# -11_04_00.net
KiCad netlist of a schematic drawn in Altium Designer
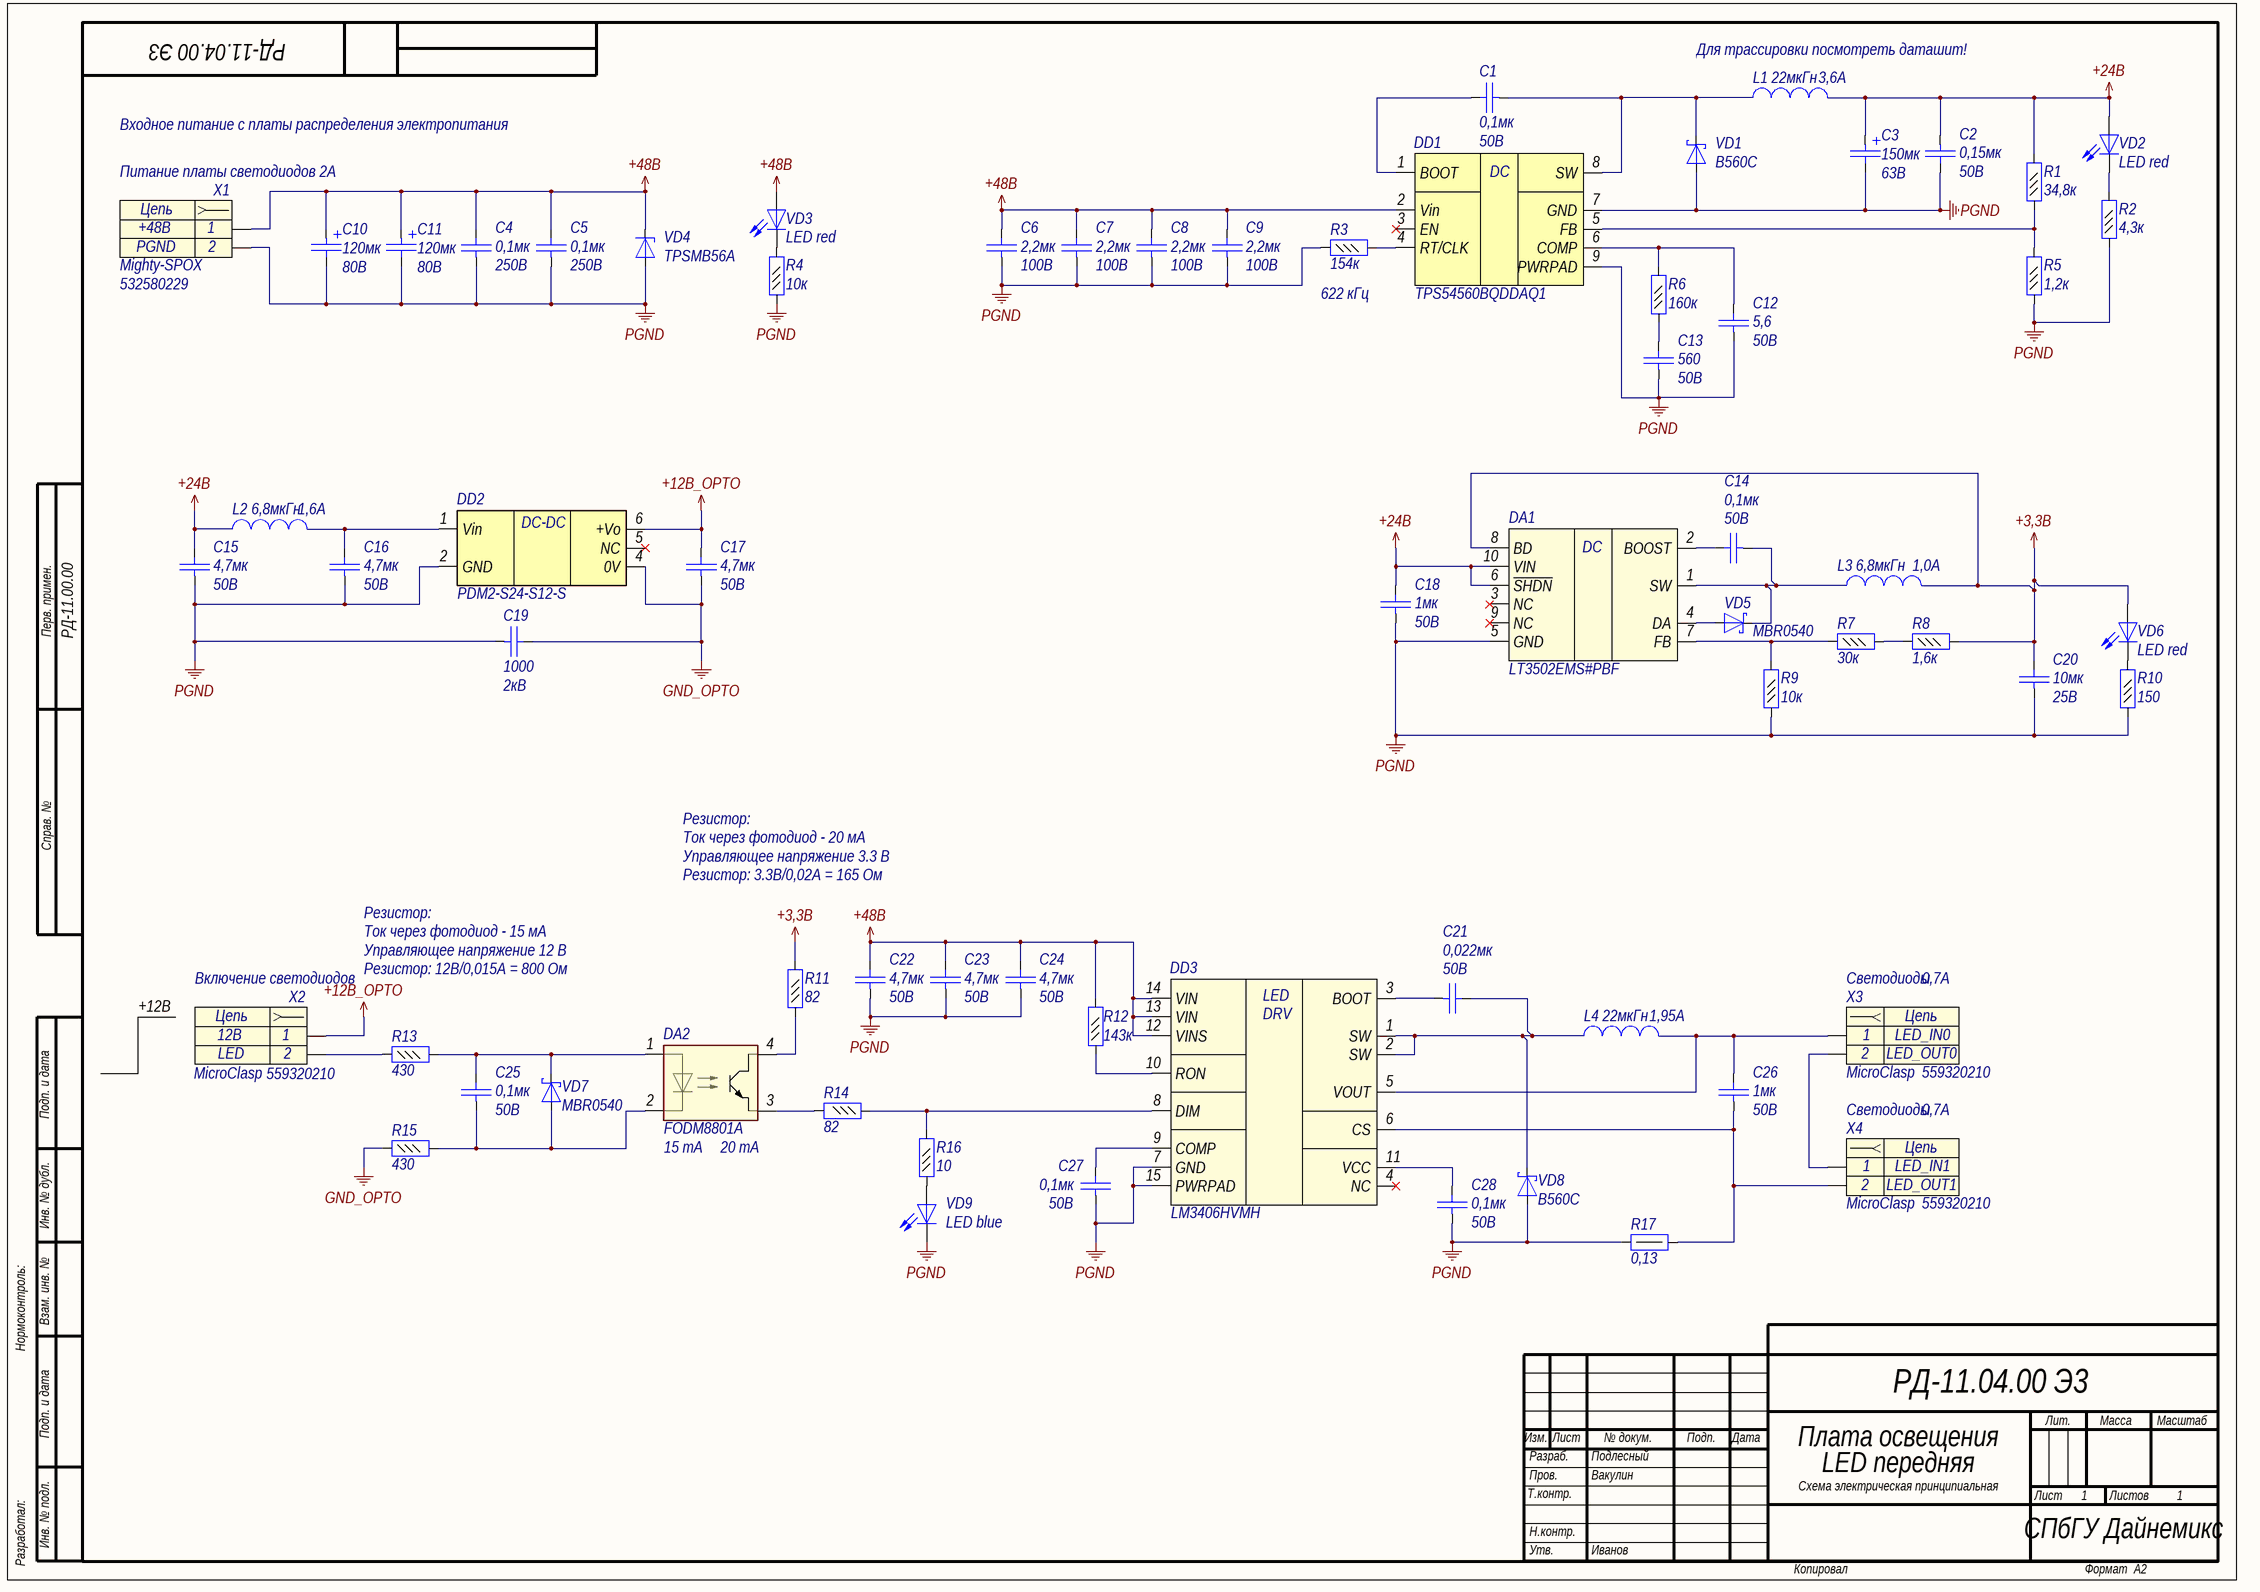
[diagram p0: РД-11.04.00.SchDoc]

(export (version "E")
  (design (tool "Eeschema 10.0.6"))
  (components
    (comp (ref "C1")
      (value "0,1мк")
      (footprint "C0603")
      (description "Конденсатор")
      (fields (field (name "VOLTAGE") "50B") (field (name "PART NUMBER") "GRM188R71H104KA93D"))
      (libsource (lib "MOP44") (part "Capacitor"))
    )
    (comp (ref "C2")
      (value "0,15мк")
      (footprint "C1812")
      (description "Конденсатор")
      (fields (field (name "VOLTAGE") "50В") (field (name "PART NUMBER") "C4532C0G1H154J250KA "))
      (libsource (lib "MOP44") (part "Capacitor"))
    )
    (comp (ref "C3")
      (value "150мк")
      (footprint "Cap_SMD_radial_polar(10x16.5)")
      (description "Конденсатор полярный")
      (fields
        (field (name "VOLTAGE") "63B")
        (field (name "PART NUMBER") "EEH-ZS1J151P")
        (field (name "Comment") "Capacitor_pol")
      )
      (libsource (lib "MOP44") (part "Capacitor_pol"))
    )
    (comp (ref "C4")
      (value "0,1мк")
      (footprint "C1206")
      (description "Конденсатор")
      (fields
        (field (name "VOLTAGE") "250В")
        (field (name "PART NUMBER") "GRM31CR72E104K")
        (field (name "Comment") "Capacitor")
      )
      (libsource (lib "MOP44") (part "Capacitor"))
    )
    (comp (ref "C5")
      (value "0,1мк")
      (footprint "C1206")
      (description "Конденсатор")
      (fields
        (field (name "VOLTAGE") "250В")
        (field (name "PART NUMBER") "GRM31CR72E104K")
        (field (name "Comment") "Capacitor")
      )
      (libsource (lib "MOP44") (part "Capacitor"))
    )
    (comp (ref "C6")
      (value "2,2мк")
      (footprint "C1812")
      (description "Конденсатор")
      (fields (field (name "VOLTAGE") "100В") (field (name "PART NUMBER") "C4532X7R2A225M"))
      (libsource (lib "MOP44") (part "Capacitor"))
    )
    (comp (ref "C7")
      (value "2,2мк")
      (footprint "C1812")
      (description "Конденсатор")
      (fields (field (name "VOLTAGE") "100В") (field (name "PART NUMBER") "C4532X7R2A225M"))
      (libsource (lib "MOP44") (part "Capacitor"))
    )
    (comp (ref "C8")
      (value "2,2мк")
      (footprint "C1812")
      (description "Конденсатор")
      (fields (field (name "VOLTAGE") "100В") (field (name "PART NUMBER") "C4532X7R2A225M"))
      (libsource (lib "MOP44") (part "Capacitor"))
    )
    (comp (ref "C9")
      (value "2,2мк")
      (footprint "C1812")
      (description "Конденсатор")
      (fields (field (name "VOLTAGE") "100В") (field (name "PART NUMBER") "C4532X7R2A225M"))
      (libsource (lib "MOP44") (part "Capacitor"))
    )
    (comp (ref "C10")
      (value "120мк")
      (footprint "K50-35(8X20)_H")
      (description "Конденсатор полярный")
      (fields
        (field (name "VOLTAGE") "80В")
        (field (name "PART NUMBER") "EEU-FS1K121LB")
        (field (name "Comment") "Capacitor_pol")
      )
      (libsource (lib "MOP44") (part "Capacitor_pol"))
    )
    (comp (ref "C11")
      (value "120мк")
      (footprint "K50-35(8X20)_H")
      (description "Конденсатор полярный")
      (fields
        (field (name "VOLTAGE") "80В")
        (field (name "PART NUMBER") "EEU-FS1K121LB")
        (field (name "Comment") "Capacitor_pol")
      )
      (libsource (lib "MOP44") (part "Capacitor_pol"))
    )
    (comp (ref "C12")
      (value "5,6")
      (footprint "C0603")
      (description "Конденсатор")
      (fields (field (name "VOLTAGE") "50B") (field (name "PART NUMBER") "GRM1885C1H5R6C*"))
      (libsource (lib "MOP44") (part "Capacitor"))
    )
    (comp (ref "C13")
      (value "560")
      (footprint "C0603")
      (description "Конденсатор")
      (fields (field (name "VOLTAGE") "50B") (field (name "PART NUMBER") "GRM1885C1H561J"))
      (libsource (lib "MOP44") (part "Capacitor"))
    )
    (comp (ref "C14")
      (value "0,1мк")
      (footprint "C0603")
      (description "Конденсатор")
      (fields (field (name "VOLTAGE") "50B") (field (name "PART NUMBER") "GRM188R71H104KA93D"))
      (libsource (lib "MOP44") (part "Capacitor"))
    )
    (comp (ref "C15")
      (value "4,7мк")
      (footprint "C1206")
      (description "Конденсатор")
      (fields (field (name "VOLTAGE") "50В") (field (name "PART NUMBER") "GRM31CR71H475KA12L"))
      (libsource (lib "MOP44") (part "Capacitor"))
    )
    (comp (ref "C16")
      (value "4,7мк")
      (footprint "C1206")
      (description "Конденсатор")
      (fields (field (name "VOLTAGE") "50В") (field (name "PART NUMBER") "GRM31CR71H475KA12L"))
      (libsource (lib "MOP44") (part "Capacitor"))
    )
    (comp (ref "C17")
      (value "4,7мк")
      (footprint "C1206")
      (description "Конденсатор")
      (fields (field (name "VOLTAGE") "50В") (field (name "PART NUMBER") "GRM31CR71H475KA12L"))
      (libsource (lib "MOP44") (part "Capacitor"))
    )
    (comp (ref "C18")
      (value "1мк")
      (footprint "C0805")
      (description "Конденсатор")
      (fields
        (field (name "VOLTAGE") "50B")
        (field (name "PART NUMBER") "GRM21BR71H105K")
        (field (name "Comment") "Capacitor")
      )
      (libsource (lib "MOP44") (part "Capacitor"))
    )
    (comp (ref "C19")
      (value "1000")
      (footprint "C1808")
      (description "Конденсатор")
      (fields (field (name "VOLTAGE") "2кB") (field (name "PART NUMBER") "GR442QR73D102KW01L"))
      (libsource (lib "MOP44") (part "Capacitor"))
    )
    (comp (ref "C20")
      (value "10мк")
      (footprint "C1206")
      (description "Конденсатор")
      (fields
        (field (name "VOLTAGE") "25В")
        (field (name "PART NUMBER") "GRM31CR71E106KA12L*")
        (field (name "Comment") "Capacitor")
      )
      (libsource (lib "MOP44") (part "Capacitor"))
    )
    (comp (ref "C21")
      (value "0,022мк")
      (footprint "C0603")
      (description "Конденсатор")
      (fields (field (name "VOLTAGE") "50B") (field (name "PART NUMBER") "GRM188R71H223K**"))
      (libsource (lib "MOP44") (part "Capacitor"))
    )
    (comp (ref "C22")
      (value "4,7мк")
      (footprint "C1206")
      (description "Конденсатор")
      (fields (field (name "VOLTAGE") "50В") (field (name "PART NUMBER") "GRM31CR71H475KA12L"))
      (libsource (lib "MOP44") (part "Capacitor"))
    )
    (comp (ref "C23")
      (value "4,7мк")
      (footprint "C1206")
      (description "Конденсатор")
      (fields (field (name "VOLTAGE") "50В") (field (name "PART NUMBER") "GRM31CR71H475KA12L"))
      (libsource (lib "MOP44") (part "Capacitor"))
    )
    (comp (ref "C24")
      (value "4,7мк")
      (footprint "C1206")
      (description "Конденсатор")
      (fields (field (name "VOLTAGE") "50В") (field (name "PART NUMBER") "GRM31CR71H475KA12L"))
      (libsource (lib "MOP44") (part "Capacitor"))
    )
    (comp (ref "C25")
      (value "0,1мк")
      (footprint "C0603")
      (description "Конденсатор")
      (fields (field (name "VOLTAGE") "50B") (field (name "PART NUMBER") "GRM188R71H104KA93D"))
      (libsource (lib "MOP44") (part "Capacitor"))
    )
    (comp (ref "C26")
      (value "1мк")
      (footprint "C0805")
      (description "Конденсатор")
      (fields
        (field (name "VOLTAGE") "50B")
        (field (name "PART NUMBER") "GRM21BR71H105K")
        (field (name "Comment") "Capacitor")
      )
      (libsource (lib "MOP44") (part "Capacitor"))
    )
    (comp (ref "C27")
      (value "0,1мк")
      (footprint "C0603")
      (description "Конденсатор")
      (fields (field (name "VOLTAGE") "50B") (field (name "PART NUMBER") "GRM188R71H104KA93D"))
      (libsource (lib "MOP44") (part "Capacitor"))
    )
    (comp (ref "C28")
      (value "0,1мк")
      (footprint "C0603")
      (description "Конденсатор")
      (fields (field (name "VOLTAGE") "50B") (field (name "PART NUMBER") "GRM188R71H104KA93D"))
      (libsource (lib "MOP44") (part "Capacitor"))
    )
    (comp (ref "DA1")
      (value "LT3502_MS")
      (footprint "MSOP10")
      (description "1.1MHz/2.2MHz, 500mA  Step-Down Regulators")
      (fields (field (name "PART NUMBER") "LT3502EMS#PBF") (field (name "MANUFACTURER") "Linear Technology"))
      (libsource (lib "MOP44") (part "LT3502_MS"))
    )
    (comp (ref "DA2")
      (value "OPTO-1")
      (footprint "Miniflat4")
      (description "Опторазвязка")
      (fields (field (name "PART NUMBER") "FODM8801A") (field (name "MANUFACTURER") "ON Semiconductor"))
      (libsource (lib "MOP44") (part "OPTO-1"))
    )
    (comp (ref "DD1")
      (value "TPS54560")
      (footprint "SO Powerpad8")
      (description "5-A, Wide Input Range, Step-Down Converter")
      (fields
        (field (name "PART NUMBER") "TPS54560BQDDAQ1")
        (field (name "MANUFACTURER") "Texas Instruments")
      )
      (libsource (lib "MOP44") (part "TPS54560"))
    )
    (comp (ref "DD2")
      (value "PDM2-Sxx-Sxx-S")
      (footprint "SIP6")
      (description "DC/DC преобразователь изолированный")
      (fields (field (name "PART NUMBER") "PDM2-S24-S12-S") (field (name "MANUFACTURER") "CUI INC"))
      (libsource (lib "MOP44") (part "PDM2-Sxx-Sxx-S"))
    )
    (comp (ref "DD3")
      (value "LM3406")
      (footprint "TSSOP14 POWERPAD")
      (description "1.5A Constant Current Buck Regulator for Driving High  Power LEDs")
      (fields (field (name "PART NUMBER") "LM3406HVMH"))
      (libsource (lib "MOP44") (part "LM3406"))
    )
    (comp (ref "L1")
      (value "22мкГн")
      (footprint "IND_12.5x12.5")
      (description "EMI Suppression Filter")
      (fields
        (field (name "RATED CURRENT") "3,6A")
        (field (name "PART NUMBER") "B82477G4223M000")
        (field (name "Comment") "Inductor")
      )
      (libsource (lib "MOP44") (part "Inductor"))
    )
    (comp (ref "L2")
      (value "6,8мкГн")
      (footprint "SDR0604")
      (description "EMI Suppression Filter")
      (fields
        (field (name "RATED CURRENT") "1,6A")
        (field (name "PART NUMBER") "SDR0604-6R8ML")
        (field (name "Comment") "Inductor")
      )
      (libsource (lib "MOP44") (part "Inductor"))
    )
    (comp (ref "L3")
      (value "6,8мкГн")
      (footprint "SDR0302")
      (description "EMI Suppression Filter")
      (fields
        (field (name "RATED CURRENT") "1,0A")
        (field (name "PART NUMBER") "SDR0302-6R8ML")
        (field (name "Comment") "Inductor")
      )
      (libsource (lib "MOP44") (part "Inductor"))
    )
    (comp (ref "L4")
      (value "22мкГн")
      (footprint "SDR1006")
      (description "EMI Suppression Filter")
      (fields
        (field (name "RATED CURRENT") "1,95A")
        (field (name "PART NUMBER") "SDR1006- 220ML")
        (field (name "Comment") "Inductor")
      )
      (libsource (lib "MOP44") (part "Inductor"))
    )
    (comp (ref "R1")
      (value "34,8к")
      (footprint "R0603")
      (description "Резистор")
      (fields (field (name "PART NUMBER") "RC0603FR-0734K8L") (field (name "POWER") "0,062Вт"))
      (libsource (lib "") (part "Resistor_0,062Вт_1"))
    )
    (comp (ref "R2")
      (value "4,3к")
      (footprint "R0603")
      (description "Резистор")
      (fields (field (name "PART NUMBER") "RC0603FR-074K3") (field (name "POWER") "0,062Вт"))
      (libsource (lib "") (part "Resistor_0,062Вт_1"))
    )
    (comp (ref "R3")
      (value "154к")
      (footprint "R0603")
      (description "Резистор")
      (fields (field (name "PART NUMBER") "RC0603FR-07154KL") (field (name "POWER") "0,062Вт"))
      (libsource (lib "MOP44") (part "Resistor_0,062Вт"))
    )
    (comp (ref "R4")
      (value "10к")
      (footprint "R0603")
      (description "Резистор")
      (fields (field (name "PART NUMBER") "RC0603FR-0710KL") (field (name "POWER") "0,062Вт"))
      (libsource (lib "") (part "Resistor_0,062Вт_1"))
    )
    (comp (ref "R5")
      (value "1,2к")
      (footprint "R0603")
      (description "Резистор")
      (fields (field (name "PART NUMBER") "RC0603FR-071K2") (field (name "POWER") "0,062Вт"))
      (libsource (lib "") (part "Resistor_0,062Вт_1"))
    )
    (comp (ref "R6")
      (value "160к")
      (footprint "R0603")
      (description "Резистор")
      (fields (field (name "PART NUMBER") "RC0603FR-07160KL") (field (name "POWER") "0,062Вт"))
      (libsource (lib "") (part "Resistor_0,062Вт_1"))
    )
    (comp (ref "R7")
      (value "30к")
      (footprint "R0603")
      (description "Резистор")
      (fields (field (name "PART NUMBER") "RC0603FR-0730KL") (field (name "POWER") "0,062Вт"))
      (libsource (lib "MOP44") (part "Resistor_0,062Вт"))
    )
    (comp (ref "R8")
      (value "1,6к")
      (footprint "R0603")
      (description "Резистор")
      (fields (field (name "PART NUMBER") "RC0603FR-071K6") (field (name "POWER") "0,062Вт"))
      (libsource (lib "MOP44") (part "Resistor_0,062Вт"))
    )
    (comp (ref "R9")
      (value "10к")
      (footprint "R0603")
      (description "Резистор")
      (fields (field (name "PART NUMBER") "RC0603FR-0710KL") (field (name "POWER") "0,062Вт"))
      (libsource (lib "") (part "Resistor_0,062Вт_1"))
    )
    (comp (ref "R10")
      (value "150")
      (footprint "R0603")
      (description "Резистор")
      (fields (field (name "PART NUMBER") "RC0603FR-07150RL") (field (name "POWER") "0,062Вт"))
      (libsource (lib "") (part "Resistor_0,062Вт_1"))
    )
    (comp (ref "R11")
      (value "82")
      (footprint "R0603")
      (description "Резистор")
      (fields (field (name "PART NUMBER") "RC0603FR-0782RL") (field (name "POWER") "0,062Вт"))
      (libsource (lib "") (part "Resistor_0,062Вт_1"))
    )
    (comp (ref "R12")
      (value "143к")
      (footprint "R0603")
      (description "Резистор")
      (fields (field (name "PART NUMBER") "RC0603FR-07143KL") (field (name "POWER") "0,062Вт"))
      (libsource (lib "") (part "Resistor_0,062Вт_1"))
    )
    (comp (ref "R13")
      (value "430")
      (footprint "R0603")
      (description "Резистор")
      (fields (field (name "PART NUMBER") "RC0603FR-07430RL") (field (name "POWER") "0,062Вт"))
      (libsource (lib "MOP44") (part "Resistor_0,062Вт"))
    )
    (comp (ref "R14")
      (value "82")
      (footprint "R0603")
      (description "Резистор")
      (fields (field (name "PART NUMBER") "RC0603FR-0782RL") (field (name "POWER") "0,062Вт"))
      (libsource (lib "") (part "Resistor_0,062Вт_2"))
    )
    (comp (ref "R15")
      (value "430")
      (footprint "R0603")
      (description "Резистор")
      (fields (field (name "PART NUMBER") "RC0603FR-07430RL") (field (name "POWER") "0,062Вт"))
      (libsource (lib "MOP44") (part "Resistor_0,062Вт"))
    )
    (comp (ref "R16")
      (value "10")
      (footprint "R0603")
      (description "Резистор")
      (fields (field (name "PART NUMBER") "RC0603FR-0710RL") (field (name "POWER") "0,062Вт"))
      (libsource (lib "") (part "Resistor_0,062Вт_1"))
    )
    (comp (ref "R17")
      (value "0,13")
      (footprint "R2010")
      (description "Резистор")
      (fields (field (name "PART NUMBER") "CRL2010-FW-R130ELF") (field (name "POWER") "0,5Вт"))
      (libsource (lib "MOP44") (part "Resistor_0,5Вт"))
    )
    (comp (ref "VD1")
      (value "DiodeSchottky")
      (footprint "SMC")
      (description "Диод Шоттки")
      (fields (field (name "PART NUMBER") "B560C"))
      (libsource (lib "MOP44") (part "DiodeSchottky"))
    )
    (comp (ref "VD2")
      (value "LED")
      (footprint "L_0603_RED")
      (description "Светодиод")
      (fields (field (name "PART NAME") "LED red") (field (name "PART NUMBER") "TO-1608BC-MRE"))
      (libsource (lib "MOP44") (part "LED"))
    )
    (comp (ref "VD3")
      (value "LED")
      (footprint "L_0603_RED")
      (description "Светодиод")
      (fields (field (name "PART NAME") "LED red") (field (name "PART NUMBER") "TO-1608BC-MRE"))
      (libsource (lib "MOP44") (part "LED"))
    )
    (comp (ref "VD4")
      (value "DiodeZener")
      (footprint "SMB")
      (description "Cтабилитрон (лавинный выпрямительный диод) односторонний")
      (fields (field (name "PART NUMBER") "TPSMB56A"))
      (libsource (lib "MOP44") (part "DiodeZener"))
    )
    (comp (ref "VD5")
      (value "DiodeSchottky")
      (footprint "SOD-123")
      (description "Диод Шоттки")
      (fields (field (name "PART NUMBER") "MBR0540"))
      (libsource (lib "MOP44") (part "DiodeSchottky"))
    )
    (comp (ref "VD6")
      (value "LED")
      (footprint "L_0603_RED")
      (description "Светодиод")
      (fields (field (name "PART NAME") "LED red") (field (name "PART NUMBER") "TO-1608BC-MRE"))
      (libsource (lib "MOP44") (part "LED"))
    )
    (comp (ref "VD7")
      (value "DiodeSchottky")
      (footprint "SOD-123")
      (description "Диод Шоттки")
      (fields (field (name "PART NUMBER") "MBR0540"))
      (libsource (lib "MOP44") (part "DiodeSchottky"))
    )
    (comp (ref "VD8")
      (value "DiodeSchottky")
      (footprint "SMC")
      (description "Диод Шоттки")
      (fields (field (name "PART NUMBER") "B560C"))
      (libsource (lib "MOP44") (part "DiodeSchottky"))
    )
    (comp (ref "VD9")
      (value "LED")
      (footprint "L_0603_BLUE")
      (description "Светодиод")
      (fields (field (name "PART NAME") "LED blue") (field (name "PART NUMBER") "TO-1608BC-BF"))
      (libsource (lib "MOP44") (part "LED"))
    )
    (comp (ref "X1")
      (value "Питание платы светодиодов 2А")
      (footprint "MOLEX_532580229")
      (description "Разъем - 2 конт. розетка")
      (fields (field (name "PART NAME") "Mighty-SPOX") (field (name "PART NUMBER") "532580229"))
      (libsource (lib "") (part "Header_2_sct_1"))
    )
    (comp (ref "X2")
      (value "Включение светодиодов")
      (footprint "MOLEX_559320210")
      (description "Разъем - 2 конт. розетка")
      (fields (field (name "PART NAME") "MicroClasp") (field (name "PART NUMBER") "559320210"))
      (libsource (lib "") (part "Header_2_sct_1"))
    )
    (comp (ref "X3")
      (value "Cветодиоды")
      (footprint "MOLEX_559320210")
      (description "Разъем - 2 конт. розетка")
      (fields (field (name "PART NAME") "MicroClasp") (field (name "PART NUMBER") "559320210"))
      (libsource (lib "MOP44") (part "Header_2_sct"))
    )
    (comp (ref "X4")
      (value "Cветодиоды")
      (footprint "MOLEX_559320210")
      (description "Разъем - 2 конт. розетка")
      (fields (field (name "PART NAME") "MicroClasp") (field (name "PART NUMBER") "559320210"))
      (libsource (lib "MOP44") (part "Header_2_sct"))
    )
  )
  (nets
    (net (code "1") (name "+3,3B") (class "Default")
      (node (ref "C20") (pin "2") (pinfunction "2_2") (pintype "passive"))
      (node (ref "DA1") (pin "8") (pinfunction "BD_8") (pintype "power_in"))
      (node (ref "L3") (pin "2") (pinfunction "2_2") (pintype "passive"))
      (node (ref "R11") (pin "2") (pinfunction "2_2") (pintype "passive"))
      (node (ref "R8") (pin "2") (pinfunction "2_2") (pintype "passive"))
      (node (ref "VD6") (pin "2") (pinfunction "A_2") (pintype "passive"))
    )
    (net (code "2") (name "+12B_OPTO") (class "Default")
      (node (ref "C17") (pin "2") (pinfunction "2_2") (pintype "passive"))
      (node (ref "DD2") (pin "6") (pinfunction "+Vo_6") (pintype "passive"))
      (node (ref "X2") (pin "1") (pinfunction "1_1") (pintype "passive"))
    )
    (net (code "3") (name "+24B") (class "Default")
      (node (ref "C15") (pin "2") (pinfunction "2_2") (pintype "passive"))
      (node (ref "C18") (pin "2") (pinfunction "2_2") (pintype "passive"))
      (node (ref "C2") (pin "1") (pinfunction "1_1") (pintype "passive"))
      (node (ref "C3") (pin "1") (pinfunction "1_1") (pintype "passive"))
      (node (ref "DA1") (pin "10") (pinfunction "VIN_10") (pintype "power_in"))
      (node (ref "DA1") (pin "6") (pinfunction "~{SHDN}_6") (pintype "power_in"))
      (node (ref "L1") (pin "2") (pinfunction "2_2") (pintype "passive"))
      (node (ref "L2") (pin "1") (pinfunction "1_1") (pintype "passive"))
      (node (ref "R1") (pin "2") (pinfunction "2_2") (pintype "passive"))
      (node (ref "VD2") (pin "2") (pinfunction "A_2") (pintype "passive"))
    )
    (net (code "4") (name "+48B") (class "Default")
      (node (ref "C10") (pin "1") (pinfunction "1_1") (pintype "passive"))
      (node (ref "C11") (pin "1") (pinfunction "1_1") (pintype "passive"))
      (node (ref "C22") (pin "2") (pinfunction "2_2") (pintype "passive"))
      (node (ref "C23") (pin "2") (pinfunction "2_2") (pintype "passive"))
      (node (ref "C24") (pin "2") (pinfunction "2_2") (pintype "passive"))
      (node (ref "C4") (pin "2") (pinfunction "2_2") (pintype "passive"))
      (node (ref "C5") (pin "2") (pinfunction "2_2") (pintype "passive"))
      (node (ref "C6") (pin "2") (pinfunction "2_2") (pintype "passive"))
      (node (ref "C7") (pin "2") (pinfunction "2_2") (pintype "passive"))
      (node (ref "C8") (pin "2") (pinfunction "2_2") (pintype "passive"))
      (node (ref "C9") (pin "2") (pinfunction "2_2") (pintype "passive"))
      (node (ref "DD1") (pin "2") (pinfunction "Vin_2") (pintype "passive"))
      (node (ref "DD3") (pin "12") (pinfunction "VINS_12") (pintype "passive"))
      (node (ref "DD3") (pin "13") (pinfunction "VIN_13") (pintype "passive"))
      (node (ref "DD3") (pin "14") (pinfunction "VIN_14") (pintype "passive"))
      (node (ref "R12") (pin "2") (pinfunction "2_2") (pintype "passive"))
      (node (ref "VD3") (pin "2") (pinfunction "A_2") (pintype "passive"))
      (node (ref "VD4") (pin "1") (pinfunction "K_1") (pintype "passive"))
      (node (ref "X1") (pin "1") (pinfunction "1_1") (pintype "passive"))
    )
    (net (code "5") (name "GND_OPTO") (class "Default")
      (node (ref "C17") (pin "1") (pinfunction "1_1") (pintype "passive"))
      (node (ref "C19") (pin "2") (pinfunction "2_2") (pintype "passive"))
      (node (ref "DD2") (pin "4") (pinfunction "0V_4") (pintype "passive"))
      (node (ref "R15") (pin "1") (pinfunction "1_1") (pintype "passive"))
    )
    (net (code "6") (name "Net-(C13-Pad2)") (class "Default")
      (node (ref "C13") (pin "2") (pinfunction "2_2") (pintype "passive"))
      (node (ref "R6") (pin "1") (pinfunction "1_1") (pintype "passive"))
    )
    (net (code "7") (name "Net-(DA1-BOOST)") (class "Default")
      (node (ref "C14") (pin "2") (pinfunction "2_2") (pintype "passive"))
      (node (ref "DA1") (pin "2") (pinfunction "BOOST_2") (pintype "power_in"))
    )
    (net (code "8") (name "Net-(DA1-DA)") (class "Default")
      (node (ref "DA1") (pin "4") (pinfunction "DA_4") (pintype "power_in"))
      (node (ref "VD5") (pin "2") (pinfunction "A_2") (pintype "passive"))
    )
    (net (code "9") (name "Net-(DA1-FB)") (class "Default")
      (node (ref "DA1") (pin "7") (pinfunction "FB_7") (pintype "power_in"))
      (node (ref "R7") (pin "1") (pinfunction "1_1") (pintype "passive"))
      (node (ref "R9") (pin "2") (pinfunction "2_2") (pintype "passive"))
    )
    (net (code "10") (name "Net-(DA1-SW)") (class "Default")
      (node (ref "C14") (pin "1") (pinfunction "1_1") (pintype "passive"))
      (node (ref "DA1") (pin "1") (pinfunction "SW_1") (pintype "power_in"))
      (node (ref "L3") (pin "1") (pinfunction "1_1") (pintype "passive"))
      (node (ref "VD5") (pin "1") (pinfunction "K_1") (pintype "passive"))
    )
    (net (code "11") (name "Net-(DA2-Pad3)") (class "Default")
      (node (ref "DA2") (pin "3") (pintype "passive"))
      (node (ref "R14") (pin "2") (pinfunction "2_2") (pintype "passive"))
    )
    (net (code "12") (name "Net-(DA2-Pad4)") (class "Default")
      (node (ref "DA2") (pin "4") (pintype "passive"))
      (node (ref "R11") (pin "1") (pinfunction "1_1") (pintype "passive"))
    )
    (net (code "13") (name "Net-(DD1-BOOT)") (class "Default")
      (node (ref "C1") (pin "2") (pinfunction "2_2") (pintype "passive"))
      (node (ref "DD1") (pin "1") (pinfunction "BOOT_1") (pintype "passive"))
    )
    (net (code "14") (name "Net-(DD1-COMP)") (class "Default")
      (node (ref "C12") (pin "2") (pinfunction "2_2") (pintype "passive"))
      (node (ref "DD1") (pin "6") (pinfunction "COMP_6") (pintype "passive"))
      (node (ref "R6") (pin "2") (pinfunction "2_2") (pintype "passive"))
    )
    (net (code "15") (name "Net-(DD1-FB)") (class "Default")
      (node (ref "DD1") (pin "5") (pinfunction "FB_5") (pintype "passive"))
      (node (ref "R1") (pin "1") (pinfunction "1_1") (pintype "passive"))
      (node (ref "R5") (pin "2") (pinfunction "2_2") (pintype "passive"))
    )
    (net (code "16") (name "Net-(DD1-RT{slash}CLK)") (class "Default")
      (node (ref "DD1") (pin "4") (pinfunction "RT/CLK_4") (pintype "passive"))
      (node (ref "R3") (pin "2") (pinfunction "2_2") (pintype "passive"))
    )
    (net (code "17") (name "Net-(DD1-SW)") (class "Default")
      (node (ref "C1") (pin "1") (pinfunction "1_1") (pintype "passive"))
      (node (ref "DD1") (pin "8") (pinfunction "SW_8") (pintype "passive"))
      (node (ref "L1") (pin "1") (pinfunction "1_1") (pintype "passive"))
      (node (ref "VD1") (pin "1") (pinfunction "K_1") (pintype "passive"))
    )
    (net (code "18") (name "Net-(DD2-Vin)") (class "Default")
      (node (ref "C16") (pin "2") (pinfunction "2_2") (pintype "passive"))
      (node (ref "DD2") (pin "1") (pinfunction "Vin_1") (pintype "passive"))
      (node (ref "L2") (pin "2") (pinfunction "2_2") (pintype "passive"))
    )
    (net (code "19") (name "Net-(DD3-BOOT)") (class "Default")
      (node (ref "C21") (pin "1") (pinfunction "1_1") (pintype "passive"))
      (node (ref "DD3") (pin "3") (pinfunction "BOOT_3") (pintype "passive"))
    )
    (net (code "20") (name "Net-(DD3-COMP)") (class "Default")
      (node (ref "C27") (pin "2") (pinfunction "2_2") (pintype "passive"))
      (node (ref "DD3") (pin "9") (pinfunction "COMP_9") (pintype "passive"))
    )
    (net (code "21") (name "Net-(DD3-CS)") (class "Default")
      (node (ref "C26") (pin "1") (pinfunction "1_1") (pintype "passive"))
      (node (ref "DD3") (pin "6") (pinfunction "CS_6") (pintype "passive"))
      (node (ref "R17") (pin "2") (pinfunction "2_2") (pintype "passive"))
      (node (ref "X4") (pin "2") (pinfunction "2_2") (pintype "passive"))
    )
    (net (code "22") (name "Net-(DD3-DIM)") (class "Default")
      (node (ref "DD3") (pin "8") (pinfunction "DIM_8") (pintype "passive"))
      (node (ref "R14") (pin "1") (pinfunction "1_1") (pintype "passive"))
      (node (ref "R16") (pin "2") (pinfunction "2_2") (pintype "passive"))
    )
    (net (code "23") (name "Net-(DD3-RON)") (class "Default")
      (node (ref "DD3") (pin "10") (pinfunction "RON_10") (pintype "passive"))
      (node (ref "R12") (pin "1") (pinfunction "1_1") (pintype "passive"))
    )
    (net (code "24") (name "Net-(DD3-VCC)") (class "Default")
      (node (ref "C28") (pin "2") (pinfunction "2_2") (pintype "passive"))
      (node (ref "DD3") (pin "11") (pinfunction "VCC_11") (pintype "passive"))
    )
    (net (code "25") (name "Net-(DD3-VOUT)") (class "Default")
      (node (ref "C26") (pin "2") (pinfunction "2_2") (pintype "passive"))
      (node (ref "DD3") (pin "5") (pinfunction "VOUT_5") (pintype "passive"))
      (node (ref "L4") (pin "2") (pinfunction "2_2") (pintype "passive"))
      (node (ref "X3") (pin "1") (pinfunction "1_1") (pintype "passive"))
    )
    (net (code "26") (name "Net-(R7-Pad2)") (class "Default")
      (node (ref "R7") (pin "2") (pinfunction "2_2") (pintype "passive"))
      (node (ref "R8") (pin "1") (pinfunction "1_1") (pintype "passive"))
    )
    (net (code "27") (name "Net-(R13-Pad1)") (class "Default")
      (node (ref "R13") (pin "1") (pinfunction "1_1") (pintype "passive"))
      (node (ref "X2") (pin "2") (pinfunction "2_2") (pintype "passive"))
    )
    (net (code "28") (name "Net-(VD2-K)") (class "Default")
      (node (ref "R2") (pin "2") (pinfunction "2_2") (pintype "passive"))
      (node (ref "VD2") (pin "1") (pinfunction "K_1") (pintype "passive"))
    )
    (net (code "29") (name "Net-(VD3-K)") (class "Default")
      (node (ref "R4") (pin "2") (pinfunction "2_2") (pintype "passive"))
      (node (ref "VD3") (pin "1") (pinfunction "K_1") (pintype "passive"))
    )
    (net (code "30") (name "Net-(VD6-K)") (class "Default")
      (node (ref "R10") (pin "2") (pinfunction "2_2") (pintype "passive"))
      (node (ref "VD6") (pin "1") (pinfunction "K_1") (pintype "passive"))
    )
    (net (code "31") (name "Net-(VD7-A)") (class "Default")
      (node (ref "C25") (pin "1") (pinfunction "1_1") (pintype "passive"))
      (node (ref "DA2") (pin "2") (pintype "passive"))
      (node (ref "R15") (pin "2") (pinfunction "2_2") (pintype "passive"))
      (node (ref "VD7") (pin "2") (pinfunction "A_2") (pintype "passive"))
    )
    (net (code "32") (name "Net-(VD7-K)") (class "Default")
      (node (ref "C25") (pin "2") (pinfunction "2_2") (pintype "passive"))
      (node (ref "DA2") (pin "1") (pintype "passive"))
      (node (ref "R13") (pin "2") (pinfunction "2_2") (pintype "passive"))
      (node (ref "VD7") (pin "1") (pinfunction "K_1") (pintype "passive"))
    )
    (net (code "33") (name "Net-(VD8-K)") (class "Default")
      (node (ref "C21") (pin "2") (pinfunction "2_2") (pintype "passive"))
      (node (ref "DD3") (pin "1") (pinfunction "SW_1") (pintype "passive"))
      (node (ref "DD3") (pin "2") (pinfunction "SW_2") (pintype "passive"))
      (node (ref "L4") (pin "1") (pinfunction "1_1") (pintype "passive"))
      (node (ref "VD8") (pin "1") (pinfunction "K_1") (pintype "passive"))
    )
    (net (code "34") (name "Net-(VD9-A)") (class "Default")
      (node (ref "R16") (pin "1") (pinfunction "1_1") (pintype "passive"))
      (node (ref "VD9") (pin "2") (pinfunction "A_2") (pintype "passive"))
    )
    (net (code "35") (name "Net-(X3-Pad2)") (class "Default")
      (node (ref "X3") (pin "2") (pinfunction "2_2") (pintype "passive"))
      (node (ref "X4") (pin "1") (pinfunction "1_1") (pintype "passive"))
    )
    (net (code "36") (name "PGND") (class "Default")
      (node (ref "C10") (pin "2") (pinfunction "2_2") (pintype "passive"))
      (node (ref "C11") (pin "2") (pinfunction "2_2") (pintype "passive"))
      (node (ref "C12") (pin "1") (pinfunction "1_1") (pintype "passive"))
      (node (ref "C13") (pin "1") (pinfunction "1_1") (pintype "passive"))
      (node (ref "C15") (pin "1") (pinfunction "1_1") (pintype "passive"))
      (node (ref "C16") (pin "1") (pinfunction "1_1") (pintype "passive"))
      (node (ref "C18") (pin "1") (pinfunction "1_1") (pintype "passive"))
      (node (ref "C19") (pin "1") (pinfunction "1_1") (pintype "passive"))
      (node (ref "C2") (pin "2") (pinfunction "2_2") (pintype "passive"))
      (node (ref "C20") (pin "1") (pinfunction "1_1") (pintype "passive"))
      (node (ref "C22") (pin "1") (pinfunction "1_1") (pintype "passive"))
      (node (ref "C23") (pin "1") (pinfunction "1_1") (pintype "passive"))
      (node (ref "C24") (pin "1") (pinfunction "1_1") (pintype "passive"))
      (node (ref "C27") (pin "1") (pinfunction "1_1") (pintype "passive"))
      (node (ref "C28") (pin "1") (pinfunction "1_1") (pintype "passive"))
      (node (ref "C3") (pin "2") (pinfunction "2_2") (pintype "passive"))
      (node (ref "C4") (pin "1") (pinfunction "1_1") (pintype "passive"))
      (node (ref "C5") (pin "1") (pinfunction "1_1") (pintype "passive"))
      (node (ref "C6") (pin "1") (pinfunction "1_1") (pintype "passive"))
      (node (ref "C7") (pin "1") (pinfunction "1_1") (pintype "passive"))
      (node (ref "C8") (pin "1") (pinfunction "1_1") (pintype "passive"))
      (node (ref "C9") (pin "1") (pinfunction "1_1") (pintype "passive"))
      (node (ref "DA1") (pin "5") (pinfunction "GND_5") (pintype "power_in"))
      (node (ref "DD1") (pin "7") (pinfunction "GND_7") (pintype "passive"))
      (node (ref "DD1") (pin "9") (pinfunction "PWRPAD_9") (pintype "passive"))
      (node (ref "DD2") (pin "2") (pinfunction "GND_2") (pintype "passive"))
      (node (ref "DD3") (pin "15") (pinfunction "PWRPAD_15") (pintype "passive"))
      (node (ref "DD3") (pin "7") (pinfunction "GND_7") (pintype "passive"))
      (node (ref "R10") (pin "1") (pinfunction "1_1") (pintype "passive"))
      (node (ref "R17") (pin "1") (pinfunction "1_1") (pintype "passive"))
      (node (ref "R2") (pin "1") (pinfunction "1_1") (pintype "passive"))
      (node (ref "R3") (pin "1") (pinfunction "1_1") (pintype "passive"))
      (node (ref "R4") (pin "1") (pinfunction "1_1") (pintype "passive"))
      (node (ref "R5") (pin "1") (pinfunction "1_1") (pintype "passive"))
      (node (ref "R9") (pin "1") (pinfunction "1_1") (pintype "passive"))
      (node (ref "VD1") (pin "2") (pinfunction "A_2") (pintype "passive"))
      (node (ref "VD4") (pin "2") (pinfunction "A_2") (pintype "passive"))
      (node (ref "VD8") (pin "2") (pinfunction "A_2") (pintype "passive"))
      (node (ref "VD9") (pin "1") (pinfunction "K_1") (pintype "passive"))
      (node (ref "X1") (pin "2") (pinfunction "2_2") (pintype "passive"))
    )
    (net (code "37") (name "unconnected-(DA1-NC-Pad3)") (class "Default")
      (node (ref "DA1") (pin "3") (pinfunction "NC_3") (pintype "power_in+no_connect"))
    )
    (net (code "38") (name "unconnected-(DA1-NC-Pad9)") (class "Default")
      (node (ref "DA1") (pin "9") (pinfunction "NC_9") (pintype "power_in+no_connect"))
    )
    (net (code "39") (name "unconnected-(DD1-EN-Pad3)") (class "Default")
      (node (ref "DD1") (pin "3") (pinfunction "EN_3") (pintype "passive+no_connect"))
    )
    (net (code "40") (name "unconnected-(DD2-NC-Pad5)") (class "Default")
      (node (ref "DD2") (pin "5") (pinfunction "NC_5") (pintype "passive+no_connect"))
    )
    (net (code "41") (name "unconnected-(DD3-NC-Pad4)") (class "Default")
      (node (ref "DD3") (pin "4") (pinfunction "NC_4") (pintype "passive+no_connect"))
    )
  )
)
